# ANALOG_OUTPUT.net
KiCad netlist of a schematic drawn in Altium Designer
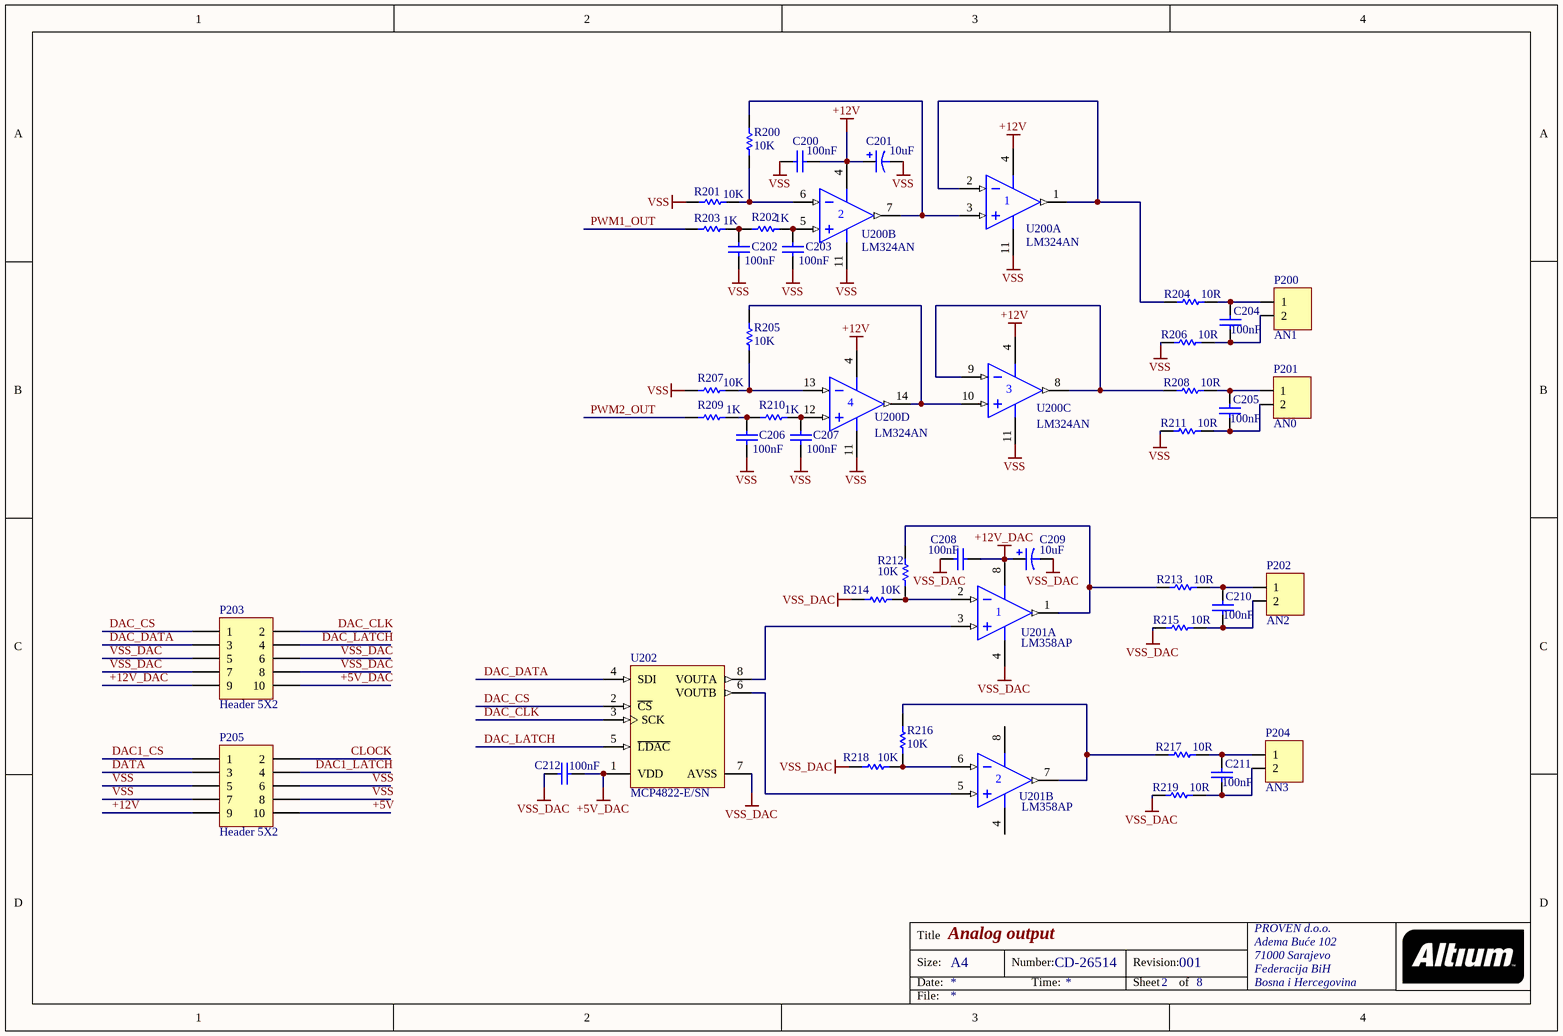
[diagram p0: ANALOG_OUTPUT.SchDoc]

(export (version "E")
  (design (tool "Eeschema 10.0.6"))
  (components
    (comp (ref "C200")
      (value "100nF")
      (footprint "1206")
      (description "Ceramic Chip Capacitor - Standard")
      (fields (field (name "PUBLISHER") "Altium Limited"))
      (libsource (lib "KEMET Chip Capacitor") (part "C1206"))
    )
    (comp (ref "C201")
      (value "10uF")
      (footprint "E")
      (description "Solid Aluminum Capacitor with Organic Semiconductor Electrolyte: 100uF, 10V, Bulk Pack")
      (fields (field (name "PUBLISHER") "Altium Limited"))
      (libsource (lib "Vishay Electrolytic Radial-Lead Capacitor") (part "94SA107X0010EBP"))
    )
    (comp (ref "C202")
      (value "100nF")
      (footprint "1206")
      (description "Ceramic Chip Capacitor - Standard")
      (fields (field (name "PUBLISHER") "Altium Limited"))
      (libsource (lib "KEMET Chip Capacitor") (part "C1206"))
    )
    (comp (ref "C203")
      (value "100nF")
      (footprint "1206")
      (description "Ceramic Chip Capacitor - Standard")
      (fields (field (name "PUBLISHER") "Altium Limited"))
      (libsource (lib "KEMET Chip Capacitor") (part "C1206"))
    )
    (comp (ref "C204")
      (value "100nF")
      (footprint "1206")
      (description "Ceramic Chip Capacitor - Standard")
      (fields (field (name "PUBLISHER") "Altium Limited"))
      (libsource (lib "KEMET Chip Capacitor") (part "C1206"))
    )
    (comp (ref "C205")
      (value "100nF")
      (footprint "1206")
      (description "Ceramic Chip Capacitor - Standard")
      (fields (field (name "PUBLISHER") "Altium Limited"))
      (libsource (lib "KEMET Chip Capacitor") (part "C1206"))
    )
    (comp (ref "C206")
      (value "100nF")
      (footprint "1206")
      (description "Ceramic Chip Capacitor - Standard")
      (fields (field (name "PUBLISHER") "Altium Limited"))
      (libsource (lib "KEMET Chip Capacitor") (part "C1206"))
    )
    (comp (ref "C207")
      (value "100nF")
      (footprint "1206")
      (description "Ceramic Chip Capacitor - Standard")
      (fields (field (name "PUBLISHER") "Altium Limited"))
      (libsource (lib "KEMET Chip Capacitor") (part "C1206"))
    )
    (comp (ref "C208")
      (value "100nF")
      (footprint "1206")
      (description "Ceramic Chip Capacitor - Standard")
      (fields (field (name "PUBLISHER") "Altium Limited"))
      (libsource (lib "KEMET Chip Capacitor") (part "C1206"))
    )
    (comp (ref "C209")
      (value "10uF")
      (footprint "Vishay Roederstein Electrolytic Radial-Lead Capacitor:CAPPR2.5-6.3X7")
      (description "Solid Aluminum Capacitor with Organic Semiconductor Electrolyte: 100uF, 10V, Bulk Pack")
      (fields (field (name "PUBLISHER") "Altium Limited"))
      (libsource (lib "Vishay Electrolytic Radial-Lead Capacitor") (part "94SA107X0010EBP"))
    )
    (comp (ref "C210")
      (value "100nF")
      (footprint "1206")
      (description "Ceramic Chip Capacitor - Standard")
      (fields (field (name "PUBLISHER") "Altium Limited"))
      (libsource (lib "KEMET Chip Capacitor") (part "C1206"))
    )
    (comp (ref "C211")
      (value "100nF")
      (footprint "1206")
      (description "Ceramic Chip Capacitor - Standard")
      (fields (field (name "PUBLISHER") "Altium Limited"))
      (libsource (lib "KEMET Chip Capacitor") (part "C1206"))
    )
    (comp (ref "C212")
      (value "100nF")
      (footprint "1206")
      (description "Ceramic Chip Capacitor - Standard")
      (fields (field (name "PUBLISHER") "Altium Limited"))
      (libsource (lib "KEMET Chip Capacitor") (part "C1206"))
    )
    (comp (ref "P200")
      (value "AN1")
      (footprint "TERMINAL BLOK 2")
      (description "Terminal blok 2")
      (libsource (lib "TERMINAL_CONNECOR_2") (part "Terminal blok 2 pina"))
    )
    (comp (ref "P201")
      (value "AN0")
      (footprint "TERMINAL BLOK 2")
      (description "Terminal blok 2")
      (libsource (lib "TERMINAL_CONNECOR_2") (part "Terminal blok 2 pina"))
    )
    (comp (ref "P202")
      (value "AN2")
      (footprint "TERMINAL BLOK 2")
      (description "Terminal blok 2")
      (libsource (lib "") (part "Terminal blok 2 pina_2"))
    )
    (comp (ref "P203")
      (value "Header 5X2")
      (footprint "HDR2X5")
      (description "Header, 5-Pin, Dual row")
      (fields (field (name "PUBLISHER") "Altium Limited"))
      (libsource (lib "Miscellaneous Connectors") (part "Header 5X2"))
    )
    (comp (ref "P204")
      (value "AN3")
      (footprint "TERMINAL BLOK 2")
      (description "Terminal blok 2")
      (libsource (lib "") (part "Terminal blok 2 pina_1"))
    )
    (comp (ref "P205")
      (value "Header 5X2")
      (footprint "HDR2X5")
      (description "Header, 5-Pin, Dual row")
      (fields (field (name "PUBLISHER") "Altium Limited"))
      (libsource (lib "Miscellaneous Connectors") (part "Header 5X2"))
    )
    (comp (ref "R200")
      (value "10K")
      (footprint "ERA-0805")
      (fields (field (name "PUBLISHER") "Altium Limited"))
      (libsource (lib "Panasonic Resistor") (part "ERAS"))
    )
    (comp (ref "R201")
      (value "10K")
      (footprint "ERA-0805")
      (fields (field (name "PUBLISHER") "Altium Limited"))
      (libsource (lib "Panasonic Resistor") (part "ERAS"))
    )
    (comp (ref "R202")
      (value "1K")
      (footprint "ERA-0805")
      (fields (field (name "PUBLISHER") "Altium Limited"))
      (libsource (lib "Panasonic Resistor") (part "ERAS"))
    )
    (comp (ref "R203")
      (value "1K")
      (footprint "ERA-0805")
      (fields (field (name "PUBLISHER") "Altium Limited"))
      (libsource (lib "Panasonic Resistor") (part "ERAS"))
    )
    (comp (ref "R204")
      (value "10R")
      (footprint "ERA-0805")
      (fields (field (name "PUBLISHER") "Altium Limited"))
      (libsource (lib "Panasonic Resistor") (part "ERA6Y"))
    )
    (comp (ref "R205")
      (value "10K")
      (footprint "ERA-0805")
      (fields (field (name "PUBLISHER") "Altium Limited"))
      (libsource (lib "Panasonic Resistor") (part "ERAS"))
    )
    (comp (ref "R206")
      (value "10R")
      (footprint "ERA-0805")
      (fields (field (name "PUBLISHER") "Altium Limited"))
      (libsource (lib "Panasonic Resistor") (part "ERA6Y"))
    )
    (comp (ref "R207")
      (value "10K")
      (footprint "ERA-0805")
      (fields (field (name "PUBLISHER") "Altium Limited"))
      (libsource (lib "Panasonic Resistor") (part "ERAS"))
    )
    (comp (ref "R208")
      (value "10R")
      (footprint "ERA-0805")
      (fields (field (name "PUBLISHER") "Altium Limited"))
      (libsource (lib "Panasonic Resistor") (part "ERA6Y"))
    )
    (comp (ref "R209")
      (value "1K")
      (footprint "ERA-0805")
      (fields (field (name "PUBLISHER") "Altium Limited"))
      (libsource (lib "Panasonic Resistor") (part "ERAS"))
    )
    (comp (ref "R210")
      (value "1K")
      (footprint "ERA-0805")
      (fields (field (name "PUBLISHER") "Altium Limited"))
      (libsource (lib "Panasonic Resistor") (part "ERAS"))
    )
    (comp (ref "R211")
      (value "10R")
      (footprint "ERA-0805")
      (fields (field (name "PUBLISHER") "Altium Limited"))
      (libsource (lib "Panasonic Resistor") (part "ERA6Y"))
    )
    (comp (ref "R212")
      (value "10K")
      (footprint "ERA-0805")
      (fields (field (name "PUBLISHER") "Altium Limited"))
      (libsource (lib "Panasonic Resistor") (part "ERAS"))
    )
    (comp (ref "R213")
      (value "10R")
      (footprint "ERA-0805")
      (fields (field (name "PUBLISHER") "Altium Limited"))
      (libsource (lib "Panasonic Resistor") (part "ERA6Y"))
    )
    (comp (ref "R214")
      (value "10K")
      (footprint "ERA-0805")
      (fields (field (name "PUBLISHER") "Altium Limited"))
      (libsource (lib "Panasonic Resistor") (part "ERAS"))
    )
    (comp (ref "R215")
      (value "10R")
      (footprint "ERA-0805")
      (fields (field (name "PUBLISHER") "Altium Limited"))
      (libsource (lib "Panasonic Resistor") (part "ERA6Y"))
    )
    (comp (ref "R216")
      (value "10K")
      (footprint "ERA-0805")
      (fields (field (name "PUBLISHER") "Altium Limited"))
      (libsource (lib "Panasonic Resistor") (part "ERAS"))
    )
    (comp (ref "R217")
      (value "10R")
      (footprint "ERA-0805")
      (fields (field (name "PUBLISHER") "Altium Limited"))
      (libsource (lib "Panasonic Resistor") (part "ERA6Y"))
    )
    (comp (ref "R218")
      (value "10K")
      (footprint "ERA-0805")
      (fields (field (name "PUBLISHER") "Altium Limited"))
      (libsource (lib "Panasonic Resistor") (part "ERAS"))
    )
    (comp (ref "R219")
      (value "10R")
      (footprint "ERA-0805")
      (fields (field (name "PUBLISHER") "Altium Limited"))
      (libsource (lib "Panasonic Resistor") (part "ERA6Y"))
    )
    (comp (ref "U200")
      (value "LM324AN")
      (footprint "N014")
      (description "Quadruple Operational Amplifier")
      (fields (field (name "PUBLISHER") "Altium Limited"))
      (libsource (lib "TI Operational Amplifier") (part "LM324AN"))
    )
    (comp (ref "U201")
      (value "LM358AP")
      (footprint "P008")
      (description "Dual Operational Amplifier")
      (fields (field (name "PUBLISHER") "Altium Limited"))
      (libsource (lib "TI Operational Amplifier") (part "LM358AP"))
    )
    (comp (ref "U202")
      (value "MCP4822-E/SN")
      (footprint "Microchip Mixed Signal:PDIP300-P8")
      (description "12-Bit DACs with Internal VREF and SPI Interface, 8-Pin SOIC 150mil, Extended Temperature")
      (fields (field (name "PUBLISHER") "Altium Limited"))
      (libsource (lib "Microchip Mixed Signal") (part "MCP4822-E/SN"))
    )
  )
  (nets
    (net (code "1") (name "+5V_DAC") (class "Default")
      (node (ref "C212") (pin "2") (pinfunction "2_2") (pintype "passive"))
      (node (ref "P203") (pin "10") (pinfunction "10_10") (pintype "passive"))
      (node (ref "U202") (pin "1") (pinfunction "VDD_1") (pintype "power_in"))
    )
    (net (code "2") (name "+12V") (class "Default")
      (node (ref "C200") (pin "2") (pinfunction "2_2") (pintype "passive"))
      (node (ref "C201") (pin "1") (pinfunction "1_1") (pintype "passive"))
      (node (ref "P205") (pin "9") (pinfunction "9_9") (pintype "passive"))
      (node (ref "U200") (pin "4") (pinfunction "V+_4") (pintype "power_in"))
    )
    (net (code "3") (name "+12V_DAC") (class "Default")
      (node (ref "C208") (pin "2") (pinfunction "2_2") (pintype "passive"))
      (node (ref "C209") (pin "1") (pinfunction "1_1") (pintype "passive"))
      (node (ref "P203") (pin "9") (pinfunction "9_9") (pintype "passive"))
      (node (ref "U201") (pin "8") (pinfunction "V+_8") (pintype "power_in"))
    )
    (net (code "4") (name "/+5V") (class "Default")
      (node (ref "P205") (pin "10") (pinfunction "10_10") (pintype "passive"))
    )
    (net (code "5") (name "/CLOCK") (class "Default")
      (node (ref "P205") (pin "2") (pinfunction "2_2") (pintype "passive"))
    )
    (net (code "6") (name "/DAC1_CS") (class "Default")
      (node (ref "P205") (pin "1") (pinfunction "1_1") (pintype "passive"))
    )
    (net (code "7") (name "/DAC1_LATCH") (class "Default")
      (node (ref "P205") (pin "4") (pinfunction "4_4") (pintype "passive"))
    )
    (net (code "8") (name "/DAC_CLK") (class "Default")
      (node (ref "P203") (pin "2") (pinfunction "2_2") (pintype "passive"))
      (node (ref "U202") (pin "3") (pinfunction "SCK_3") (pintype "input"))
    )
    (net (code "9") (name "/DAC_CS") (class "Default")
      (node (ref "P203") (pin "1") (pinfunction "1_1") (pintype "passive"))
      (node (ref "U202") (pin "2") (pinfunction "~{CS}_2") (pintype "input"))
    )
    (net (code "10") (name "/DAC_DATA") (class "Default")
      (node (ref "P203") (pin "3") (pinfunction "3_3") (pintype "passive"))
      (node (ref "U202") (pin "4") (pinfunction "SDI_4") (pintype "input"))
    )
    (net (code "11") (name "/DAC_LATCH") (class "Default")
      (node (ref "P203") (pin "4") (pinfunction "4_4") (pintype "passive"))
      (node (ref "U202") (pin "5") (pinfunction "~{LDAC}_5") (pintype "input"))
    )
    (net (code "12") (name "/DATA") (class "Default")
      (node (ref "P205") (pin "3") (pinfunction "3_3") (pintype "passive"))
    )
    (net (code "13") (name "/PWM1_OUT") (class "Default")
      (node (ref "R203") (pin "1") (pinfunction "1_1") (pintype "passive"))
    )
    (net (code "14") (name "/PWM2_OUT") (class "Default")
      (node (ref "R209") (pin "1") (pinfunction "1_1") (pintype "passive"))
    )
    (net (code "15") (name "Net-(C202-Pad2)") (class "Default")
      (node (ref "C202") (pin "2") (pinfunction "2_2") (pintype "passive"))
      (node (ref "R202") (pin "1") (pinfunction "1_1") (pintype "passive"))
      (node (ref "R203") (pin "2") (pinfunction "2_2") (pintype "passive"))
    )
    (net (code "16") (name "Net-(C204-Pad1)") (class "Default")
      (node (ref "C204") (pin "1") (pinfunction "1_1") (pintype "passive"))
      (node (ref "P200") (pin "2") (pinfunction "2_2") (pintype "passive"))
      (node (ref "R206") (pin "2") (pinfunction "2_2") (pintype "passive"))
    )
    (net (code "17") (name "Net-(C204-Pad2)") (class "Default")
      (node (ref "C204") (pin "2") (pinfunction "2_2") (pintype "passive"))
      (node (ref "P200") (pin "1") (pinfunction "1_1") (pintype "passive"))
      (node (ref "R204") (pin "2") (pinfunction "2_2") (pintype "passive"))
    )
    (net (code "18") (name "Net-(C205-Pad1)") (class "Default")
      (node (ref "C205") (pin "1") (pinfunction "1_1") (pintype "passive"))
      (node (ref "P201") (pin "2") (pinfunction "2_2") (pintype "passive"))
      (node (ref "R211") (pin "2") (pinfunction "2_2") (pintype "passive"))
    )
    (net (code "19") (name "Net-(C205-Pad2)") (class "Default")
      (node (ref "C205") (pin "2") (pinfunction "2_2") (pintype "passive"))
      (node (ref "P201") (pin "1") (pinfunction "1_1") (pintype "passive"))
      (node (ref "R208") (pin "2") (pinfunction "2_2") (pintype "passive"))
    )
    (net (code "20") (name "Net-(C206-Pad2)") (class "Default")
      (node (ref "C206") (pin "2") (pinfunction "2_2") (pintype "passive"))
      (node (ref "R209") (pin "2") (pinfunction "2_2") (pintype "passive"))
      (node (ref "R210") (pin "1") (pinfunction "1_1") (pintype "passive"))
    )
    (net (code "21") (name "Net-(C210-Pad1)") (class "Default")
      (node (ref "C210") (pin "1") (pinfunction "1_1") (pintype "passive"))
      (node (ref "P202") (pin "2") (pinfunction "2_2") (pintype "passive"))
      (node (ref "R215") (pin "2") (pinfunction "2_2") (pintype "passive"))
    )
    (net (code "22") (name "Net-(C210-Pad2)") (class "Default")
      (node (ref "C210") (pin "2") (pinfunction "2_2") (pintype "passive"))
      (node (ref "P202") (pin "1") (pinfunction "1_1") (pintype "passive"))
      (node (ref "R213") (pin "2") (pinfunction "2_2") (pintype "passive"))
    )
    (net (code "23") (name "Net-(C211-Pad1)") (class "Default")
      (node (ref "C211") (pin "1") (pinfunction "1_1") (pintype "passive"))
      (node (ref "P204") (pin "2") (pinfunction "2_2") (pintype "passive"))
      (node (ref "R219") (pin "2") (pinfunction "2_2") (pintype "passive"))
    )
    (net (code "24") (name "Net-(C211-Pad2)") (class "Default")
      (node (ref "C211") (pin "2") (pinfunction "2_2") (pintype "passive"))
      (node (ref "P204") (pin "1") (pinfunction "1_1") (pintype "passive"))
      (node (ref "R217") (pin "2") (pinfunction "2_2") (pintype "passive"))
    )
    (net (code "25") (name "Net-(U200A-IN+)") (class "Default")
      (node (ref "R200") (pin "2") (pinfunction "2_2") (pintype "passive"))
      (node (ref "U200") (pin "3") (pinfunction "IN+_3") (pintype "input"))
      (node (ref "U200") (pin "7") (pinfunction "OUT_7") (pintype "output"))
    )
    (net (code "26") (name "Net-(U200A-IN-)") (class "Default")
      (node (ref "R204") (pin "1") (pinfunction "1_1") (pintype "passive"))
      (node (ref "U200") (pin "1") (pinfunction "OUT_1") (pintype "output"))
      (node (ref "U200") (pin "2") (pinfunction "IN-_2") (pintype "input"))
    )
    (net (code "27") (name "Net-(U200B-IN+)") (class "Default")
      (node (ref "C203") (pin "2") (pinfunction "2_2") (pintype "passive"))
      (node (ref "R202") (pin "2") (pinfunction "2_2") (pintype "passive"))
      (node (ref "U200") (pin "5") (pinfunction "IN+_5") (pintype "input"))
    )
    (net (code "28") (name "Net-(U200B-IN-)") (class "Default")
      (node (ref "R200") (pin "1") (pinfunction "1_1") (pintype "passive"))
      (node (ref "R201") (pin "2") (pinfunction "2_2") (pintype "passive"))
      (node (ref "U200") (pin "6") (pinfunction "IN-_6") (pintype "input"))
    )
    (net (code "29") (name "Net-(U200C-IN+)") (class "Default")
      (node (ref "R205") (pin "2") (pinfunction "2_2") (pintype "passive"))
      (node (ref "U200") (pin "10") (pinfunction "IN+_10") (pintype "input"))
      (node (ref "U200") (pin "14") (pinfunction "OUT_14") (pintype "output"))
    )
    (net (code "30") (name "Net-(U200C-IN-)") (class "Default")
      (node (ref "R208") (pin "1") (pinfunction "1_1") (pintype "passive"))
      (node (ref "U200") (pin "8") (pinfunction "OUT_8") (pintype "output"))
      (node (ref "U200") (pin "9") (pinfunction "IN-_9") (pintype "input"))
    )
    (net (code "31") (name "Net-(U200D-IN+)") (class "Default")
      (node (ref "C207") (pin "2") (pinfunction "2_2") (pintype "passive"))
      (node (ref "R210") (pin "2") (pinfunction "2_2") (pintype "passive"))
      (node (ref "U200") (pin "12") (pinfunction "IN+_12") (pintype "input"))
    )
    (net (code "32") (name "Net-(U200D-IN-)") (class "Default")
      (node (ref "R205") (pin "1") (pinfunction "1_1") (pintype "passive"))
      (node (ref "R207") (pin "2") (pinfunction "2_2") (pintype "passive"))
      (node (ref "U200") (pin "13") (pinfunction "IN-_13") (pintype "input"))
    )
    (net (code "33") (name "Net-(U201A-IN+)") (class "Default")
      (node (ref "U201") (pin "3") (pinfunction "IN+_3") (pintype "input"))
      (node (ref "U202") (pin "8") (pinfunction "VOUTA_8") (pintype "output"))
    )
    (net (code "34") (name "Net-(U201A-IN-)") (class "Default")
      (node (ref "R212") (pin "1") (pinfunction "1_1") (pintype "passive"))
      (node (ref "R214") (pin "1") (pinfunction "1_1") (pintype "passive"))
      (node (ref "U201") (pin "2") (pinfunction "IN-_2") (pintype "input"))
    )
    (net (code "35") (name "Net-(U201A-OUT)") (class "Default")
      (node (ref "R212") (pin "2") (pinfunction "2_2") (pintype "passive"))
      (node (ref "R213") (pin "1") (pinfunction "1_1") (pintype "passive"))
      (node (ref "U201") (pin "1") (pinfunction "OUT_1") (pintype "output"))
    )
    (net (code "36") (name "Net-(U201B-IN+)") (class "Default")
      (node (ref "U201") (pin "5") (pinfunction "IN+_5") (pintype "input"))
      (node (ref "U202") (pin "6") (pinfunction "VOUTB_6") (pintype "output"))
    )
    (net (code "37") (name "Net-(U201B-IN-)") (class "Default")
      (node (ref "R216") (pin "1") (pinfunction "1_1") (pintype "passive"))
      (node (ref "R218") (pin "1") (pinfunction "1_1") (pintype "passive"))
      (node (ref "U201") (pin "6") (pinfunction "IN-_6") (pintype "input"))
    )
    (net (code "38") (name "Net-(U201B-OUT)") (class "Default")
      (node (ref "R216") (pin "2") (pinfunction "2_2") (pintype "passive"))
      (node (ref "R217") (pin "1") (pinfunction "1_1") (pintype "passive"))
      (node (ref "U201") (pin "7") (pinfunction "OUT_7") (pintype "output"))
    )
    (net (code "39") (name "VSS") (class "Default")
      (node (ref "C200") (pin "1") (pinfunction "1_1") (pintype "passive"))
      (node (ref "C201") (pin "2") (pinfunction "2_2") (pintype "passive"))
      (node (ref "C202") (pin "1") (pinfunction "1_1") (pintype "passive"))
      (node (ref "C203") (pin "1") (pinfunction "1_1") (pintype "passive"))
      (node (ref "C206") (pin "1") (pinfunction "1_1") (pintype "passive"))
      (node (ref "C207") (pin "1") (pinfunction "1_1") (pintype "passive"))
      (node (ref "P205") (pin "5") (pinfunction "5_5") (pintype "passive"))
      (node (ref "P205") (pin "6") (pinfunction "6_6") (pintype "passive"))
      (node (ref "P205") (pin "7") (pinfunction "7_7") (pintype "passive"))
      (node (ref "P205") (pin "8") (pinfunction "8_8") (pintype "passive"))
      (node (ref "R201") (pin "1") (pinfunction "1_1") (pintype "passive"))
      (node (ref "R206") (pin "1") (pinfunction "1_1") (pintype "passive"))
      (node (ref "R207") (pin "1") (pinfunction "1_1") (pintype "passive"))
      (node (ref "R211") (pin "1") (pinfunction "1_1") (pintype "passive"))
      (node (ref "U200") (pin "11") (pinfunction "V-_11") (pintype "power_in"))
    )
    (net (code "40") (name "VSS_DAC") (class "Default")
      (node (ref "C208") (pin "1") (pinfunction "1_1") (pintype "passive"))
      (node (ref "C209") (pin "2") (pinfunction "2_2") (pintype "passive"))
      (node (ref "C212") (pin "1") (pinfunction "1_1") (pintype "passive"))
      (node (ref "P203") (pin "5") (pinfunction "5_5") (pintype "passive"))
      (node (ref "P203") (pin "6") (pinfunction "6_6") (pintype "passive"))
      (node (ref "P203") (pin "7") (pinfunction "7_7") (pintype "passive"))
      (node (ref "P203") (pin "8") (pinfunction "8_8") (pintype "passive"))
      (node (ref "R214") (pin "2") (pinfunction "2_2") (pintype "passive"))
      (node (ref "R215") (pin "1") (pinfunction "1_1") (pintype "passive"))
      (node (ref "R218") (pin "2") (pinfunction "2_2") (pintype "passive"))
      (node (ref "R219") (pin "1") (pinfunction "1_1") (pintype "passive"))
      (node (ref "U201") (pin "4") (pinfunction "V-_4") (pintype "power_in"))
      (node (ref "U202") (pin "7") (pinfunction "AVSS_7") (pintype "power_in"))
    )
    (net (code "41") (name "unconnected-(U201B-V+-Pad8)") (class "Default")
      (node (ref "U201") (pin "8") (pinfunction "V+_8") (pintype "power_in"))
    )
    (net (code "42") (name "unconnected-(U201B-V--Pad4)") (class "Default")
      (node (ref "U201") (pin "4") (pinfunction "V-_4") (pintype "power_in"))
    )
  )
)
